# Axis_Channel.net
KiCad netlist of a schematic drawn in Altium Designer
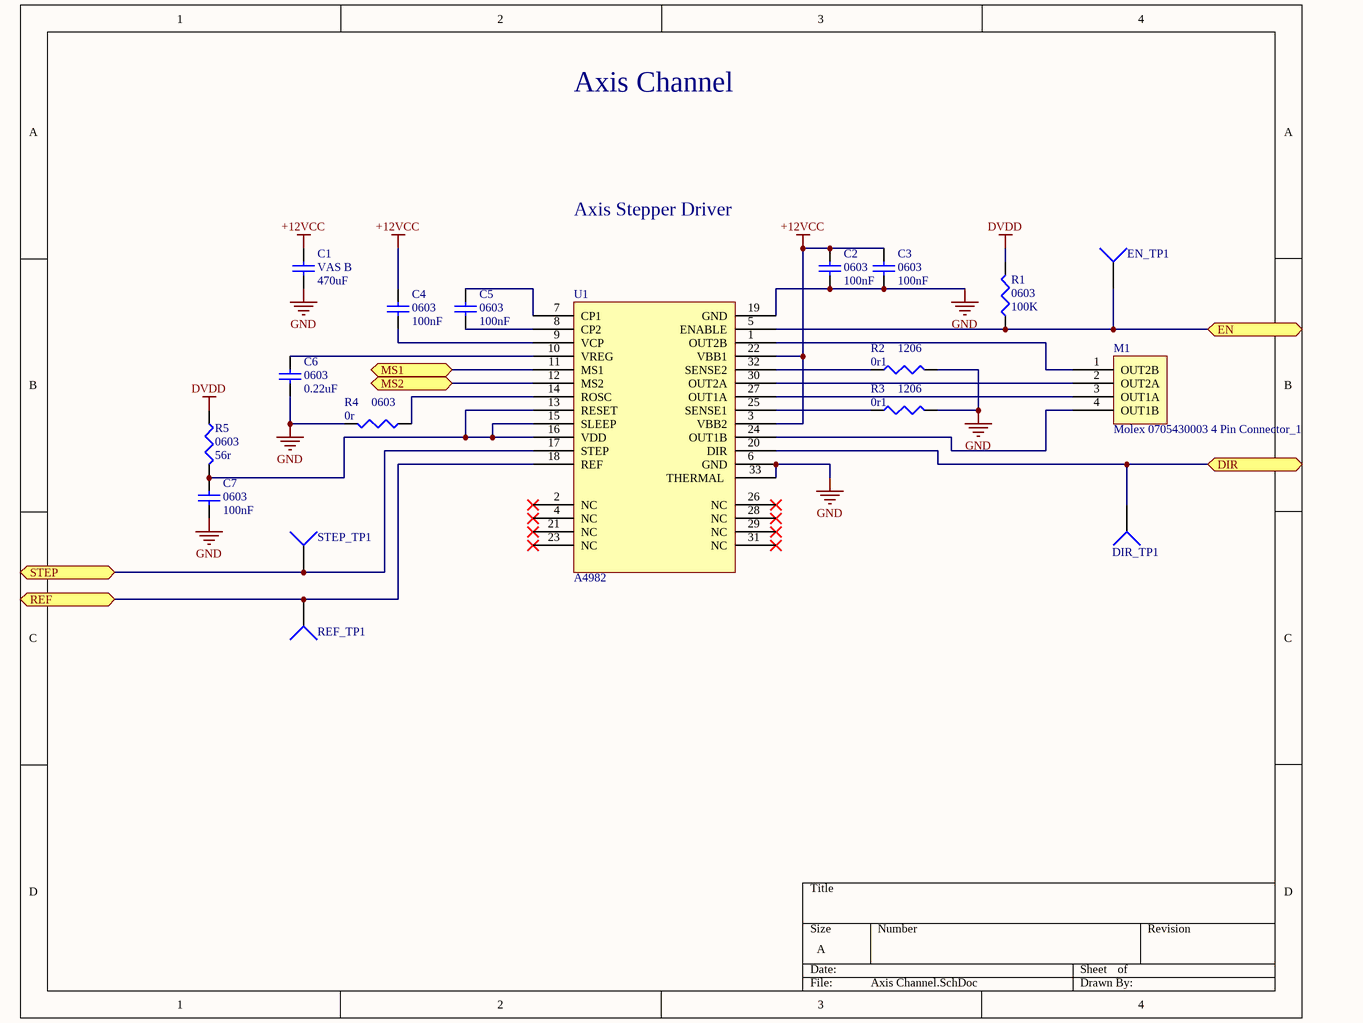
[diagram p0: Axis Channel.SchDoc]

(export (version "E")
  (design (tool "Eeschema 10.0.6"))
  (components
    (comp (ref "C1")
      (value "VAS B")
      (footprint "Panasonic VS B")
      (description "Capacitor (Semiconductor SIM Model)")
      (fields (field (name "ALTIUM_VALUE") "470uF") (field (name "PUBLISHER") "Altium Limited"))
      (libsource (lib "Miscellaneous Devices") (part "Cap Semi"))
    )
    (comp (ref "C2")
      (value "0603")
      (footprint "1608[0603]")
      (description "Capacitor (Semiconductor SIM Model)")
      (fields (field (name "ALTIUM_VALUE") "100nF") (field (name "PUBLISHER") "Altium Limited"))
      (libsource (lib "Miscellaneous Devices") (part "Cap Semi"))
    )
    (comp (ref "C3")
      (value "0603")
      (footprint "1608[0603]")
      (description "Capacitor (Semiconductor SIM Model)")
      (fields (field (name "ALTIUM_VALUE") "100nF") (field (name "PUBLISHER") "Altium Limited"))
      (libsource (lib "Miscellaneous Devices") (part "Cap Semi"))
    )
    (comp (ref "C4")
      (value "0603")
      (footprint "1608[0603]")
      (description "Capacitor (Semiconductor SIM Model)")
      (fields (field (name "ALTIUM_VALUE") "100nF") (field (name "PUBLISHER") "Altium Limited"))
      (libsource (lib "Miscellaneous Devices") (part "Cap Semi"))
    )
    (comp (ref "C5")
      (value "0603")
      (footprint "1608[0603]")
      (description "Capacitor (Semiconductor SIM Model)")
      (fields (field (name "ALTIUM_VALUE") "100nF") (field (name "PUBLISHER") "Altium Limited"))
      (libsource (lib "Miscellaneous Devices") (part "Cap Semi"))
    )
    (comp (ref "C6")
      (value "0603")
      (footprint "1608[0603]")
      (description "Capacitor (Semiconductor SIM Model)")
      (fields (field (name "ALTIUM_VALUE") "0.22uF") (field (name "PUBLISHER") "Altium Limited"))
      (libsource (lib "Miscellaneous Devices") (part "Cap Semi"))
    )
    (comp (ref "C7")
      (value "0603")
      (footprint "1608[0603]")
      (description "Capacitor (Semiconductor SIM Model)")
      (fields (field (name "ALTIUM_VALUE") "100nF") (field (name "PUBLISHER") "Altium Limited"))
      (libsource (lib "Miscellaneous Devices") (part "Cap Semi"))
    )
    (comp (ref "DIR_TP1")
      (value "TP4")
      (footprint "PIN1")
      (description "Socket")
      (fields (field (name "PUBLISHER") "Altium Limited"))
      (libsource (lib "Miscellaneous Connectors") (part "Socket"))
    )
    (comp (ref "EN_TP1")
      (value "TP4")
      (footprint "PIN1")
      (description "Socket")
      (fields (field (name "PUBLISHER") "Altium Limited"))
      (libsource (lib "Miscellaneous Connectors") (part "Socket"))
    )
    (comp (ref "M1")
      (value "Molex 0705430003 4 Pin Connector_1")
      (footprint "Molex 0705430003")
      (libsource (lib "RADMBo Schematic Library") (part "Molex 0705430003 4 Pin Connector_1"))
    )
    (comp (ref "R1")
      (value "0603")
      (footprint "J1-0603")
      (description "Resistor")
      (fields (field (name "ALTIUM_VALUE") "100K") (field (name "PUBLISHER") "Altium Limited"))
      (libsource (lib "Miscellaneous Devices") (part "Res3"))
    )
    (comp (ref "R2")
      (value "1206")
      (footprint "1206 SMD Resistor")
      (description "Resistor")
      (fields (field (name "ALTIUM_VALUE") "0r1") (field (name "PUBLISHER") "Altium Limited"))
      (libsource (lib "Miscellaneous Devices") (part "Res3"))
    )
    (comp (ref "R3")
      (value "1206")
      (footprint "1206 SMD Resistor")
      (description "Resistor")
      (fields (field (name "ALTIUM_VALUE") "0r1") (field (name "PUBLISHER") "Altium Limited"))
      (libsource (lib "Miscellaneous Devices") (part "Res3"))
    )
    (comp (ref "R4")
      (value "0603")
      (footprint "J1-0603")
      (description "Resistor")
      (fields (field (name "ALTIUM_VALUE") "0r") (field (name "PUBLISHER") "Altium Limited"))
      (libsource (lib "Miscellaneous Devices") (part "Res3"))
    )
    (comp (ref "R5")
      (value "0603")
      (footprint "J1-0603")
      (description "Resistor")
      (fields (field (name "ALTIUM_VALUE") "56r") (field (name "PUBLISHER") "Altium Limited"))
      (libsource (lib "Miscellaneous Devices") (part "Res3"))
    )
    (comp (ref "REF_TP1")
      (value "TP4")
      (footprint "PIN1")
      (description "Socket")
      (fields (field (name "PUBLISHER") "Altium Limited"))
      (libsource (lib "Miscellaneous Connectors") (part "Socket"))
    )
    (comp (ref "STEP_TP1")
      (value "TP4")
      (footprint "PIN1")
      (description "Socket")
      (fields (field (name "PUBLISHER") "Altium Limited"))
      (libsource (lib "Miscellaneous Connectors") (part "Socket"))
    )
    (comp (ref "U1")
      (value "A4982")
      (footprint "QFN50P508X508X100_HS-33N")
      (description "Alllegor A4982 Stepper Driver")
      (libsource (lib "RADMBo Schematic Library") (part "A4982"))
    )
  )
  (nets
    (net (code "1") (name "+12VCC") (class "Default")
      (node (ref "C1") (pin "2") (pinfunction "2_2") (pintype "passive"))
      (node (ref "C2") (pin "2") (pinfunction "2_2") (pintype "passive"))
      (node (ref "C3") (pin "2") (pinfunction "2_2") (pintype "passive"))
      (node (ref "C4") (pin "2") (pinfunction "2_2") (pintype "passive"))
      (node (ref "U1") (pin "22") (pinfunction "VBB1_22") (pintype "passive"))
      (node (ref "U1") (pin "3") (pinfunction "VBB2_3") (pintype "passive"))
    )
    (net (code "2") (name "/DIR") (class "Default")
      (node (ref "DIR_TP1") (pin "1") (pinfunction "1_1") (pintype "passive"))
      (node (ref "U1") (pin "20") (pinfunction "DIR_20") (pintype "passive"))
    )
    (net (code "3") (name "/EN") (class "Default")
      (node (ref "EN_TP1") (pin "1") (pinfunction "1_1") (pintype "passive"))
      (node (ref "R1") (pin "1") (pinfunction "1_1") (pintype "passive"))
      (node (ref "U1") (pin "5") (pinfunction "ENABLE_5") (pintype "passive"))
    )
    (net (code "4") (name "/MS1") (class "Default")
      (node (ref "U1") (pin "11") (pinfunction "MS1_11") (pintype "passive"))
    )
    (net (code "5") (name "/MS2") (class "Default")
      (node (ref "U1") (pin "12") (pinfunction "MS2_12") (pintype "passive"))
    )
    (net (code "6") (name "/REF") (class "Default")
      (node (ref "REF_TP1") (pin "1") (pinfunction "1_1") (pintype "passive"))
      (node (ref "U1") (pin "18") (pinfunction "REF_18") (pintype "passive"))
    )
    (net (code "7") (name "/STEP") (class "Default")
      (node (ref "STEP_TP1") (pin "1") (pinfunction "1_1") (pintype "passive"))
      (node (ref "U1") (pin "17") (pinfunction "STEP_17") (pintype "passive"))
    )
    (net (code "8") (name "DVDD") (class "Default")
      (node (ref "R1") (pin "2") (pinfunction "2_2") (pintype "passive"))
      (node (ref "R5") (pin "1") (pinfunction "1_1") (pintype "passive"))
    )
    (net (code "9") (name "GND") (class "Default")
      (node (ref "C1") (pin "1") (pinfunction "1_1") (pintype "passive"))
      (node (ref "C2") (pin "1") (pinfunction "1_1") (pintype "passive"))
      (node (ref "C3") (pin "1") (pinfunction "1_1") (pintype "passive"))
      (node (ref "C6") (pin "1") (pinfunction "1_1") (pintype "passive"))
      (node (ref "C7") (pin "1") (pinfunction "1_1") (pintype "passive"))
      (node (ref "R2") (pin "2") (pinfunction "2_2") (pintype "passive"))
      (node (ref "R3") (pin "2") (pinfunction "2_2") (pintype "passive"))
      (node (ref "R4") (pin "2") (pinfunction "2_2") (pintype "passive"))
      (node (ref "U1") (pin "19") (pinfunction "GND_19") (pintype "passive"))
      (node (ref "U1") (pin "33") (pinfunction "THERMAL_33") (pintype "passive"))
      (node (ref "U1") (pin "6") (pinfunction "GND_6") (pintype "passive"))
    )
    (net (code "10") (name "Net-(M1-OUT1A)") (class "Default")
      (node (ref "M1") (pin "3") (pinfunction "OUT1A_3") (pintype "passive"))
      (node (ref "U1") (pin "27") (pinfunction "OUT1A_27") (pintype "passive"))
    )
    (net (code "11") (name "Net-(M1-OUT1B)") (class "Default")
      (node (ref "M1") (pin "4") (pinfunction "OUT1B_4") (pintype "passive"))
      (node (ref "U1") (pin "24") (pinfunction "OUT1B_24") (pintype "passive"))
    )
    (net (code "12") (name "Net-(M1-OUT2A)") (class "Default")
      (node (ref "M1") (pin "2") (pinfunction "OUT2A_2") (pintype "passive"))
      (node (ref "U1") (pin "30") (pinfunction "OUT2A_30") (pintype "passive"))
    )
    (net (code "13") (name "Net-(M1-OUT2B)") (class "Default")
      (node (ref "M1") (pin "1") (pinfunction "OUT2B_1") (pintype "passive"))
      (node (ref "U1") (pin "1") (pinfunction "OUT2B_1") (pintype "passive"))
    )
    (net (code "14") (name "Net-(U1-CP1)") (class "Default")
      (node (ref "C5") (pin "2") (pinfunction "2_2") (pintype "passive"))
      (node (ref "U1") (pin "7") (pinfunction "CP1_7") (pintype "passive"))
    )
    (net (code "15") (name "Net-(U1-CP2)") (class "Default")
      (node (ref "C5") (pin "1") (pinfunction "1_1") (pintype "passive"))
      (node (ref "U1") (pin "8") (pinfunction "CP2_8") (pintype "passive"))
    )
    (net (code "16") (name "Net-(U1-RESET)") (class "Default")
      (node (ref "C7") (pin "2") (pinfunction "2_2") (pintype "passive"))
      (node (ref "R5") (pin "2") (pinfunction "2_2") (pintype "passive"))
      (node (ref "U1") (pin "13") (pinfunction "RESET_13") (pintype "passive"))
      (node (ref "U1") (pin "15") (pinfunction "SLEEP_15") (pintype "passive"))
      (node (ref "U1") (pin "16") (pinfunction "VDD_16") (pintype "passive"))
    )
    (net (code "17") (name "Net-(U1-ROSC)") (class "Default")
      (node (ref "R4") (pin "1") (pinfunction "1_1") (pintype "passive"))
      (node (ref "U1") (pin "14") (pinfunction "ROSC_14") (pintype "passive"))
    )
    (net (code "18") (name "Net-(U1-SENSE1)") (class "Default")
      (node (ref "R3") (pin "1") (pinfunction "1_1") (pintype "passive"))
      (node (ref "U1") (pin "25") (pinfunction "SENSE1_25") (pintype "passive"))
    )
    (net (code "19") (name "Net-(U1-SENSE2)") (class "Default")
      (node (ref "R2") (pin "1") (pinfunction "1_1") (pintype "passive"))
      (node (ref "U1") (pin "32") (pinfunction "SENSE2_32") (pintype "passive"))
    )
    (net (code "20") (name "Net-(U1-VCP)") (class "Default")
      (node (ref "C4") (pin "1") (pinfunction "1_1") (pintype "passive"))
      (node (ref "U1") (pin "9") (pinfunction "VCP_9") (pintype "passive"))
    )
    (net (code "21") (name "Net-(U1-VREG)") (class "Default")
      (node (ref "C6") (pin "2") (pinfunction "2_2") (pintype "passive"))
      (node (ref "U1") (pin "10") (pinfunction "VREG_10") (pintype "passive"))
    )
    (net (code "22") (name "unconnected-(U1-NC-Pad2)") (class "Default")
      (node (ref "U1") (pin "2") (pinfunction "NC_2") (pintype "passive+no_connect"))
    )
    (net (code "23") (name "unconnected-(U1-NC-Pad4)") (class "Default")
      (node (ref "U1") (pin "4") (pinfunction "NC_4") (pintype "passive+no_connect"))
    )
    (net (code "24") (name "unconnected-(U1-NC-Pad21)") (class "Default")
      (node (ref "U1") (pin "21") (pinfunction "NC_21") (pintype "passive+no_connect"))
    )
    (net (code "25") (name "unconnected-(U1-NC-Pad23)") (class "Default")
      (node (ref "U1") (pin "23") (pinfunction "NC_23") (pintype "passive+no_connect"))
    )
    (net (code "26") (name "unconnected-(U1-NC-Pad26)") (class "Default")
      (node (ref "U1") (pin "26") (pinfunction "NC_26") (pintype "passive+no_connect"))
    )
    (net (code "27") (name "unconnected-(U1-NC-Pad28)") (class "Default")
      (node (ref "U1") (pin "28") (pinfunction "NC_28") (pintype "passive+no_connect"))
    )
    (net (code "28") (name "unconnected-(U1-NC-Pad29)") (class "Default")
      (node (ref "U1") (pin "29") (pinfunction "NC_29") (pintype "passive+no_connect"))
    )
    (net (code "29") (name "unconnected-(U1-NC-Pad31)") (class "Default")
      (node (ref "U1") (pin "31") (pinfunction "NC_31") (pintype "passive+no_connect"))
    )
  )
)
